# Sheet1.net
KiCad netlist of a schematic drawn in Altium Designer
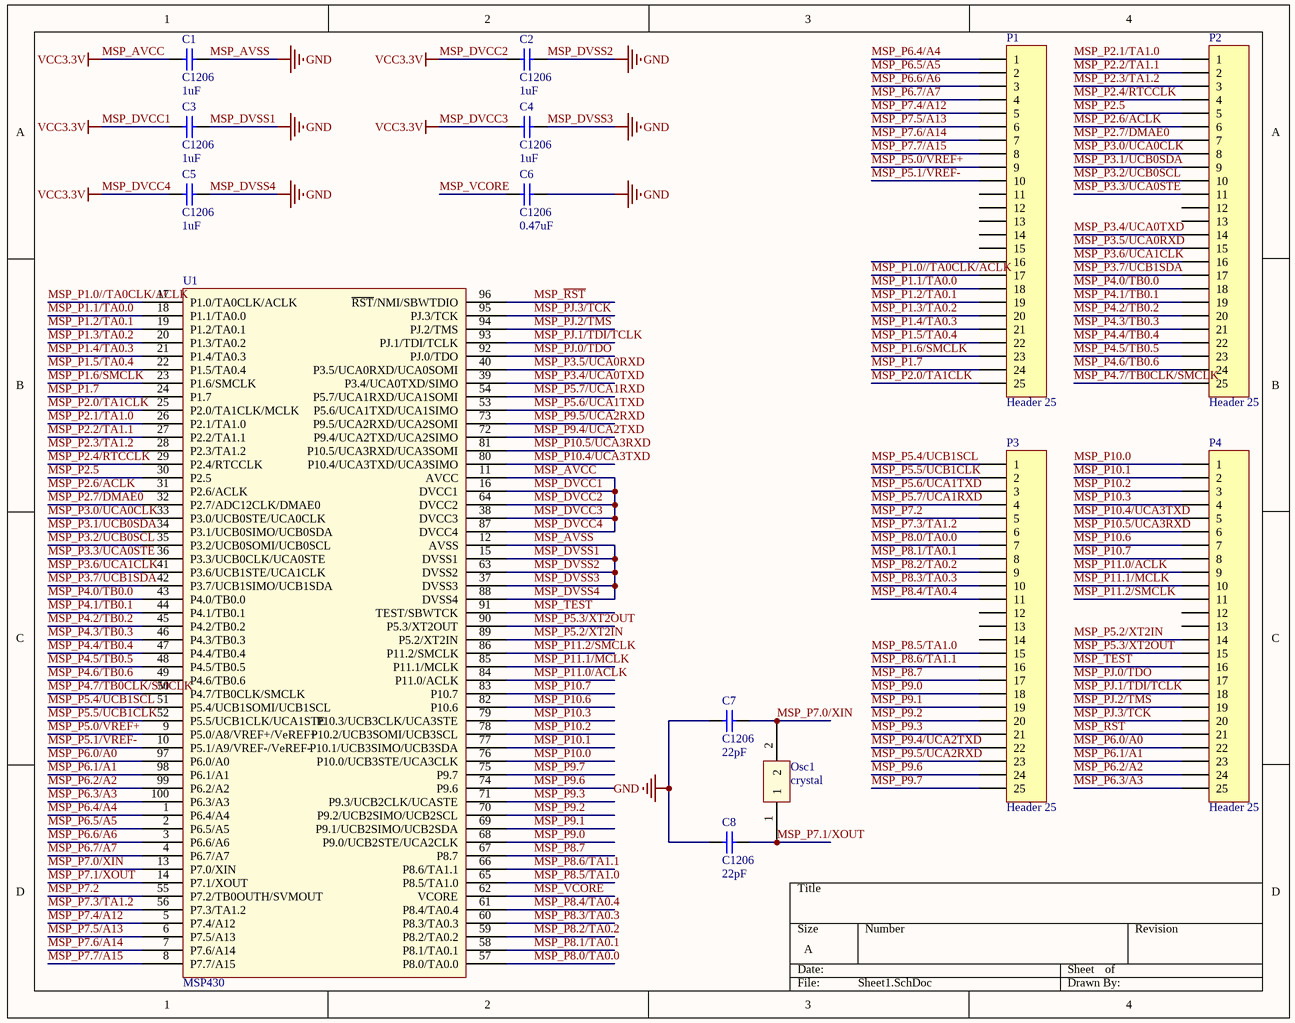
[diagram p0: Sheet1.SchDoc]

(export (version "E")
  (design (tool "Eeschema 10.0.6"))
  (components
    (comp (ref "C1")
      (value "C1206")
      (footprint "1206")
      (description "Ceramic Chip Capacitor - Standard")
      (fields (field (name "ALTIUM_VALUE") "1uF") (field (name "PUBLISHER") "Altium Limited"))
      (libsource (lib "KEMET Chip Capacitor") (part "C1206"))
    )
    (comp (ref "C2")
      (value "C1206")
      (footprint "1206")
      (description "Ceramic Chip Capacitor - Standard")
      (fields (field (name "ALTIUM_VALUE") "1uF") (field (name "PUBLISHER") "Altium Limited"))
      (libsource (lib "KEMET Chip Capacitor") (part "C1206"))
    )
    (comp (ref "C3")
      (value "C1206")
      (footprint "1206")
      (description "Ceramic Chip Capacitor - Standard")
      (fields (field (name "ALTIUM_VALUE") "1uF") (field (name "PUBLISHER") "Altium Limited"))
      (libsource (lib "KEMET Chip Capacitor") (part "C1206"))
    )
    (comp (ref "C4")
      (value "C1206")
      (footprint "1206")
      (description "Ceramic Chip Capacitor - Standard")
      (fields (field (name "ALTIUM_VALUE") "1uF") (field (name "PUBLISHER") "Altium Limited"))
      (libsource (lib "KEMET Chip Capacitor") (part "C1206"))
    )
    (comp (ref "C5")
      (value "C1206")
      (footprint "1206")
      (description "Ceramic Chip Capacitor - Standard")
      (fields (field (name "ALTIUM_VALUE") "1uF") (field (name "PUBLISHER") "Altium Limited"))
      (libsource (lib "KEMET Chip Capacitor") (part "C1206"))
    )
    (comp (ref "C6")
      (value "C1206")
      (footprint "1206")
      (description "Ceramic Chip Capacitor - Standard")
      (fields (field (name "ALTIUM_VALUE") "0.47uF") (field (name "PUBLISHER") "Altium Limited"))
      (libsource (lib "KEMET Chip Capacitor") (part "C1206"))
    )
    (comp (ref "C7")
      (value "C1206")
      (footprint "1206")
      (description "Ceramic Chip Capacitor - Standard")
      (fields (field (name "ALTIUM_VALUE") "22pF") (field (name "PUBLISHER") "Altium Limited"))
      (libsource (lib "KEMET Chip Capacitor") (part "C1206"))
    )
    (comp (ref "C8")
      (value "C1206")
      (footprint "1206")
      (description "Ceramic Chip Capacitor - Standard")
      (fields (field (name "ALTIUM_VALUE") "22pF") (field (name "PUBLISHER") "Altium Limited"))
      (libsource (lib "KEMET Chip Capacitor") (part "C1206"))
    )
    (comp (ref "Osc1")
      (value "crystal")
      (footprint "Crystal_32K:PCBComponent_1")
      (libsource (lib "Crystal_32K") (part "crystal"))
    )
    (comp (ref "P1")
      (value "Header 25")
      (footprint "HDR1X25")
      (description "Header, 25-Pin")
      (fields (field (name "PUBLISHER") "Altium Limited"))
      (libsource (lib "Miscellaneous Connectors") (part "Header 25"))
    )
    (comp (ref "P2")
      (value "Header 25")
      (footprint "HDR1X25")
      (description "Header, 25-Pin")
      (fields (field (name "PUBLISHER") "Altium Limited"))
      (libsource (lib "Miscellaneous Connectors") (part "Header 25"))
    )
    (comp (ref "P3")
      (value "Header 25")
      (footprint "HDR1X25")
      (description "Header, 25-Pin")
      (fields (field (name "PUBLISHER") "Altium Limited"))
      (libsource (lib "Miscellaneous Connectors") (part "Header 25"))
    )
    (comp (ref "P4")
      (value "Header 25")
      (footprint "HDR1X25")
      (description "Header, 25-Pin")
      (fields (field (name "PUBLISHER") "Altium Limited"))
      (libsource (lib "Miscellaneous Connectors") (part "Header 25"))
    )
    (comp (ref "U1")
      (value "MSP430")
      (footprint "MSP430F5438A:TSQFP50P1600X1600X160-100N")
      (libsource (lib "MSP430F5438A") (part "MSP430"))
    )
  )
  (nets
    (net (code "1") (name "/MSP_P1.0{slash}{slash}TA0CLK{slash}ACLK") (class "Default")
      (node (ref "P1") (pin "17") (pinfunction "17_17") (pintype "passive"))
      (node (ref "U1") (pin "17") (pinfunction "P1.0/TA0CLK/ACLK_17") (pintype "passive"))
    )
    (net (code "2") (name "/MSP_P1.1{slash}TA0.0") (class "Default")
      (node (ref "P1") (pin "18") (pinfunction "18_18") (pintype "passive"))
      (node (ref "U1") (pin "18") (pinfunction "P1.1/TA0.0_18") (pintype "passive"))
    )
    (net (code "3") (name "/MSP_P1.2{slash}TA0.1") (class "Default")
      (node (ref "P1") (pin "19") (pinfunction "19_19") (pintype "passive"))
      (node (ref "U1") (pin "19") (pinfunction "P1.2/TA0.1_19") (pintype "passive"))
    )
    (net (code "4") (name "/MSP_P1.3{slash}TA0.2") (class "Default")
      (node (ref "P1") (pin "20") (pinfunction "20_20") (pintype "passive"))
      (node (ref "U1") (pin "20") (pinfunction "P1.3/TA0.2_20") (pintype "passive"))
    )
    (net (code "5") (name "/MSP_P1.4{slash}TA0.3") (class "Default")
      (node (ref "P1") (pin "21") (pinfunction "21_21") (pintype "passive"))
      (node (ref "U1") (pin "21") (pinfunction "P1.4/TA0.3_21") (pintype "passive"))
    )
    (net (code "6") (name "/MSP_P1.5{slash}TA0.4") (class "Default")
      (node (ref "P1") (pin "22") (pinfunction "22_22") (pintype "passive"))
      (node (ref "U1") (pin "22") (pinfunction "P1.5/TA0.4_22") (pintype "passive"))
    )
    (net (code "7") (name "/MSP_P1.6{slash}SMCLK") (class "Default")
      (node (ref "P1") (pin "23") (pinfunction "23_23") (pintype "passive"))
      (node (ref "U1") (pin "23") (pinfunction "P1.6/SMCLK_23") (pintype "passive"))
    )
    (net (code "8") (name "/MSP_P1.7") (class "Default")
      (node (ref "P1") (pin "24") (pinfunction "24_24") (pintype "passive"))
      (node (ref "U1") (pin "24") (pinfunction "P1.7_24") (pintype "passive"))
    )
    (net (code "9") (name "/MSP_P2.0{slash}TA1CLK") (class "Default")
      (node (ref "P1") (pin "25") (pinfunction "25_25") (pintype "passive"))
      (node (ref "U1") (pin "25") (pinfunction "P2.0/TA1CLK/MCLK_25") (pintype "passive"))
    )
    (net (code "10") (name "/MSP_P2.1{slash}TA1.0") (class "Default")
      (node (ref "P2") (pin "1") (pinfunction "1_1") (pintype "passive"))
      (node (ref "U1") (pin "26") (pinfunction "P2.1/TA1.0_26") (pintype "passive"))
    )
    (net (code "11") (name "/MSP_P2.2{slash}TA1.1") (class "Default")
      (node (ref "P2") (pin "2") (pinfunction "2_2") (pintype "passive"))
      (node (ref "U1") (pin "27") (pinfunction "P2.2/TA1.1_27") (pintype "passive"))
    )
    (net (code "12") (name "/MSP_P2.3{slash}TA1.2") (class "Default")
      (node (ref "P2") (pin "3") (pinfunction "3_3") (pintype "passive"))
      (node (ref "U1") (pin "28") (pinfunction "P2.3/TA1.2_28") (pintype "passive"))
    )
    (net (code "13") (name "/MSP_P2.4{slash}RTCCLK") (class "Default")
      (node (ref "P2") (pin "4") (pinfunction "4_4") (pintype "passive"))
      (node (ref "U1") (pin "29") (pinfunction "P2.4/RTCCLK_29") (pintype "passive"))
    )
    (net (code "14") (name "/MSP_P2.5") (class "Default")
      (node (ref "P2") (pin "5") (pinfunction "5_5") (pintype "passive"))
      (node (ref "U1") (pin "30") (pinfunction "P2.5_30") (pintype "passive"))
    )
    (net (code "15") (name "/MSP_P2.6{slash}ACLK") (class "Default")
      (node (ref "P2") (pin "6") (pinfunction "6_6") (pintype "passive"))
      (node (ref "U1") (pin "31") (pinfunction "P2.6/ACLK_31") (pintype "passive"))
    )
    (net (code "16") (name "/MSP_P2.7{slash}DMAE0") (class "Default")
      (node (ref "P2") (pin "7") (pinfunction "7_7") (pintype "passive"))
      (node (ref "U1") (pin "32") (pinfunction "P2.7/ADC12CLK/DMAE0_32") (pintype "passive"))
    )
    (net (code "17") (name "/MSP_P3.0{slash}UCA0CLK") (class "Default")
      (node (ref "P2") (pin "8") (pinfunction "8_8") (pintype "passive"))
      (node (ref "U1") (pin "33") (pinfunction "P3.0/UCB0STE/UCA0CLK_33") (pintype "passive"))
    )
    (net (code "18") (name "/MSP_P3.1{slash}UCB0SDA") (class "Default")
      (node (ref "P2") (pin "9") (pinfunction "9_9") (pintype "passive"))
      (node (ref "U1") (pin "34") (pinfunction "P3.1/UCB0SIMO/UCB0SDA_34") (pintype "passive"))
    )
    (net (code "19") (name "/MSP_P3.2{slash}UCB0SCL") (class "Default")
      (node (ref "P2") (pin "10") (pinfunction "10_10") (pintype "passive"))
      (node (ref "U1") (pin "35") (pinfunction "P3.2/UCB0SOMI/UCB0SCL_35") (pintype "passive"))
    )
    (net (code "20") (name "/MSP_P3.3{slash}UCA0STE") (class "Default")
      (node (ref "P2") (pin "11") (pinfunction "11_11") (pintype "passive"))
      (node (ref "U1") (pin "36") (pinfunction "P3.3/UCB0CLK/UCA0STE_36") (pintype "passive"))
    )
    (net (code "21") (name "/MSP_P3.4{slash}UCA0TXD") (class "Default")
      (node (ref "P2") (pin "14") (pinfunction "14_14") (pintype "passive"))
      (node (ref "U1") (pin "39") (pinfunction "P3.4/UCA0TXD/SIMO_39") (pintype "passive"))
    )
    (net (code "22") (name "/MSP_P3.5{slash}UCA0RXD") (class "Default")
      (node (ref "P2") (pin "15") (pinfunction "15_15") (pintype "passive"))
      (node (ref "U1") (pin "40") (pinfunction "P3.5/UCA0RXD/UCA0SOMI_40") (pintype "passive"))
    )
    (net (code "23") (name "/MSP_P3.6{slash}UCA1CLK") (class "Default")
      (node (ref "P2") (pin "16") (pinfunction "16_16") (pintype "passive"))
      (node (ref "U1") (pin "41") (pinfunction "P3.6/UCB1STE/UCA1CLK_41") (pintype "passive"))
    )
    (net (code "24") (name "/MSP_P3.7{slash}UCB1SDA") (class "Default")
      (node (ref "P2") (pin "17") (pinfunction "17_17") (pintype "passive"))
      (node (ref "U1") (pin "42") (pinfunction "P3.7/UCB1SIMO/UCB1SDA_42") (pintype "passive"))
    )
    (net (code "25") (name "/MSP_P4.0{slash}TB0.0") (class "Default")
      (node (ref "P2") (pin "18") (pinfunction "18_18") (pintype "passive"))
      (node (ref "U1") (pin "43") (pinfunction "P4.0/TB0.0_43") (pintype "passive"))
    )
    (net (code "26") (name "/MSP_P4.1{slash}TB0.1") (class "Default")
      (node (ref "P2") (pin "19") (pinfunction "19_19") (pintype "passive"))
      (node (ref "U1") (pin "44") (pinfunction "P4.1/TB0.1_44") (pintype "passive"))
    )
    (net (code "27") (name "/MSP_P4.2{slash}TB0.2") (class "Default")
      (node (ref "P2") (pin "20") (pinfunction "20_20") (pintype "passive"))
      (node (ref "U1") (pin "45") (pinfunction "P4.2/TB0.2_45") (pintype "passive"))
    )
    (net (code "28") (name "/MSP_P4.3{slash}TB0.3") (class "Default")
      (node (ref "P2") (pin "21") (pinfunction "21_21") (pintype "passive"))
      (node (ref "U1") (pin "46") (pinfunction "P4.3/TB0.3_46") (pintype "passive"))
    )
    (net (code "29") (name "/MSP_P4.4{slash}TB0.4") (class "Default")
      (node (ref "P2") (pin "22") (pinfunction "22_22") (pintype "passive"))
      (node (ref "U1") (pin "47") (pinfunction "P4.4/TB0.4_47") (pintype "passive"))
    )
    (net (code "30") (name "/MSP_P4.5{slash}TB0.5") (class "Default")
      (node (ref "P2") (pin "23") (pinfunction "23_23") (pintype "passive"))
      (node (ref "U1") (pin "48") (pinfunction "P4.5/TB0.5_48") (pintype "passive"))
    )
    (net (code "31") (name "/MSP_P4.6{slash}TB0.6") (class "Default")
      (node (ref "P2") (pin "24") (pinfunction "24_24") (pintype "passive"))
      (node (ref "U1") (pin "49") (pinfunction "P4.6/TB0.6_49") (pintype "passive"))
    )
    (net (code "32") (name "/MSP_P4.7{slash}TB0CLK{slash}SMCLK") (class "Default")
      (node (ref "P2") (pin "25") (pinfunction "25_25") (pintype "passive"))
      (node (ref "U1") (pin "50") (pinfunction "P4.7/TB0CLK/SMCLK_50") (pintype "passive"))
    )
    (net (code "33") (name "/MSP_P5.0{slash}VREF+") (class "Default")
      (node (ref "P1") (pin "9") (pinfunction "9_9") (pintype "passive"))
      (node (ref "U1") (pin "9") (pinfunction "P5.0/A8/VREF+/VeREF+_9") (pintype "passive"))
    )
    (net (code "34") (name "/MSP_P5.1{slash}VREF-") (class "Default")
      (node (ref "P1") (pin "10") (pinfunction "10_10") (pintype "passive"))
      (node (ref "U1") (pin "10") (pinfunction "P5.1/A9/VREF-/VeREF-_10") (pintype "passive"))
    )
    (net (code "35") (name "/MSP_P5.2{slash}XT2IN") (class "Default")
      (node (ref "P4") (pin "14") (pinfunction "14_14") (pintype "passive"))
      (node (ref "U1") (pin "89") (pinfunction "P5.2/XT2IN_89") (pintype "passive"))
    )
    (net (code "36") (name "/MSP_P5.3{slash}XT2OUT") (class "Default")
      (node (ref "P4") (pin "15") (pinfunction "15_15") (pintype "passive"))
      (node (ref "U1") (pin "90") (pinfunction "P5.3/XT2OUT_90") (pintype "passive"))
    )
    (net (code "37") (name "/MSP_P5.4{slash}UCB1SCL") (class "Default")
      (node (ref "P3") (pin "1") (pinfunction "1_1") (pintype "passive"))
      (node (ref "U1") (pin "51") (pinfunction "P5.4/UCB1SOMI/UCB1SCL_51") (pintype "passive"))
    )
    (net (code "38") (name "/MSP_P5.5{slash}UCB1CLK") (class "Default")
      (node (ref "P3") (pin "2") (pinfunction "2_2") (pintype "passive"))
      (node (ref "U1") (pin "52") (pinfunction "P5.5/UCB1CLK/UCA1STE_52") (pintype "passive"))
    )
    (net (code "39") (name "/MSP_P5.6{slash}UCA1TXD") (class "Default")
      (node (ref "P3") (pin "3") (pinfunction "3_3") (pintype "passive"))
      (node (ref "U1") (pin "53") (pinfunction "P5.6/UCA1TXD/UCA1SIMO_53") (pintype "passive"))
    )
    (net (code "40") (name "/MSP_P5.7{slash}UCA1RXD") (class "Default")
      (node (ref "P3") (pin "4") (pinfunction "4_4") (pintype "passive"))
      (node (ref "U1") (pin "54") (pinfunction "P5.7/UCA1RXD/UCA1SOMI_54") (pintype "passive"))
    )
    (net (code "41") (name "/MSP_P6.0{slash}A0") (class "Default")
      (node (ref "P4") (pin "22") (pinfunction "22_22") (pintype "passive"))
      (node (ref "U1") (pin "97") (pinfunction "P6.0/A0_97") (pintype "passive"))
    )
    (net (code "42") (name "/MSP_P6.1{slash}A1") (class "Default")
      (node (ref "P4") (pin "23") (pinfunction "23_23") (pintype "passive"))
      (node (ref "U1") (pin "98") (pinfunction "P6.1/A1_98") (pintype "passive"))
    )
    (net (code "43") (name "/MSP_P6.2{slash}A2") (class "Default")
      (node (ref "P4") (pin "24") (pinfunction "24_24") (pintype "passive"))
      (node (ref "U1") (pin "99") (pinfunction "P6.2/A2_99") (pintype "passive"))
    )
    (net (code "44") (name "/MSP_P6.3{slash}A3") (class "Default")
      (node (ref "P4") (pin "25") (pinfunction "25_25") (pintype "passive"))
      (node (ref "U1") (pin "100") (pinfunction "P6.3/A3_100") (pintype "passive"))
    )
    (net (code "45") (name "/MSP_P6.4{slash}A4") (class "Default")
      (node (ref "P1") (pin "1") (pinfunction "1_1") (pintype "passive"))
      (node (ref "U1") (pin "1") (pinfunction "P6.4/A4_1") (pintype "passive"))
    )
    (net (code "46") (name "/MSP_P6.5{slash}A5") (class "Default")
      (node (ref "P1") (pin "2") (pinfunction "2_2") (pintype "passive"))
      (node (ref "U1") (pin "2") (pinfunction "P6.5/A5_2") (pintype "passive"))
    )
    (net (code "47") (name "/MSP_P6.6{slash}A6") (class "Default")
      (node (ref "P1") (pin "3") (pinfunction "3_3") (pintype "passive"))
      (node (ref "U1") (pin "3") (pinfunction "P6.6/A6_3") (pintype "passive"))
    )
    (net (code "48") (name "/MSP_P6.7{slash}A7") (class "Default")
      (node (ref "P1") (pin "4") (pinfunction "4_4") (pintype "passive"))
      (node (ref "U1") (pin "4") (pinfunction "P6.7/A7_4") (pintype "passive"))
    )
    (net (code "49") (name "/MSP_P7.0{slash}XIN") (class "Default")
      (node (ref "C7") (pin "2") (pinfunction "2_2") (pintype "passive"))
      (node (ref "Osc1") (pin "2") (pinfunction "2_2") (pintype "passive"))
      (node (ref "U1") (pin "13") (pinfunction "P7.0/XIN_13") (pintype "passive"))
    )
    (net (code "50") (name "/MSP_P7.1{slash}XOUT") (class "Default")
      (node (ref "C8") (pin "2") (pinfunction "2_2") (pintype "passive"))
      (node (ref "Osc1") (pin "1") (pinfunction "1_1") (pintype "passive"))
      (node (ref "U1") (pin "14") (pinfunction "P7.1/XOUT_14") (pintype "passive"))
    )
    (net (code "51") (name "/MSP_P7.2") (class "Default")
      (node (ref "P3") (pin "5") (pinfunction "5_5") (pintype "passive"))
      (node (ref "U1") (pin "55") (pinfunction "P7.2/TB0OUTH/SVMOUT_55") (pintype "passive"))
    )
    (net (code "52") (name "/MSP_P7.3{slash}TA1.2") (class "Default")
      (node (ref "P3") (pin "6") (pinfunction "6_6") (pintype "passive"))
      (node (ref "U1") (pin "56") (pinfunction "P7.3/TA1.2_56") (pintype "passive"))
    )
    (net (code "53") (name "/MSP_P7.4{slash}A12") (class "Default")
      (node (ref "P1") (pin "5") (pinfunction "5_5") (pintype "passive"))
      (node (ref "U1") (pin "5") (pinfunction "P7.4/A12_5") (pintype "passive"))
    )
    (net (code "54") (name "/MSP_P7.5{slash}A13") (class "Default")
      (node (ref "P1") (pin "6") (pinfunction "6_6") (pintype "passive"))
      (node (ref "U1") (pin "6") (pinfunction "P7.5/A13_6") (pintype "passive"))
    )
    (net (code "55") (name "/MSP_P7.6{slash}A14") (class "Default")
      (node (ref "P1") (pin "7") (pinfunction "7_7") (pintype "passive"))
      (node (ref "U1") (pin "7") (pinfunction "P7.6/A14_7") (pintype "passive"))
    )
    (net (code "56") (name "/MSP_P7.7{slash}A15") (class "Default")
      (node (ref "P1") (pin "8") (pinfunction "8_8") (pintype "passive"))
      (node (ref "U1") (pin "8") (pinfunction "P7.7/A15_8") (pintype "passive"))
    )
    (net (code "57") (name "/MSP_P8.0{slash}TA0.0") (class "Default")
      (node (ref "P3") (pin "7") (pinfunction "7_7") (pintype "passive"))
      (node (ref "U1") (pin "57") (pinfunction "P8.0/TA0.0_57") (pintype "passive"))
    )
    (net (code "58") (name "/MSP_P8.1{slash}TA0.1") (class "Default")
      (node (ref "P3") (pin "8") (pinfunction "8_8") (pintype "passive"))
      (node (ref "U1") (pin "58") (pinfunction "P8.1/TA0.1_58") (pintype "passive"))
    )
    (net (code "59") (name "/MSP_P8.2{slash}TA0.2") (class "Default")
      (node (ref "P3") (pin "9") (pinfunction "9_9") (pintype "passive"))
      (node (ref "U1") (pin "59") (pinfunction "P8.2/TA0.2_59") (pintype "passive"))
    )
    (net (code "60") (name "/MSP_P8.3{slash}TA0.3") (class "Default")
      (node (ref "P3") (pin "10") (pinfunction "10_10") (pintype "passive"))
      (node (ref "U1") (pin "60") (pinfunction "P8.3/TA0.3_60") (pintype "passive"))
    )
    (net (code "61") (name "/MSP_P8.4{slash}TA0.4") (class "Default")
      (node (ref "P3") (pin "11") (pinfunction "11_11") (pintype "passive"))
      (node (ref "U1") (pin "61") (pinfunction "P8.4/TA0.4_61") (pintype "passive"))
    )
    (net (code "62") (name "/MSP_P8.5{slash}TA1.0") (class "Default")
      (node (ref "P3") (pin "15") (pinfunction "15_15") (pintype "passive"))
      (node (ref "U1") (pin "65") (pinfunction "P8.5/TA1.0_65") (pintype "passive"))
    )
    (net (code "63") (name "/MSP_P8.6{slash}TA1.1") (class "Default")
      (node (ref "P3") (pin "16") (pinfunction "16_16") (pintype "passive"))
      (node (ref "U1") (pin "66") (pinfunction "P8.6/TA1.1_66") (pintype "passive"))
    )
    (net (code "64") (name "/MSP_P8.7") (class "Default")
      (node (ref "P3") (pin "17") (pinfunction "17_17") (pintype "passive"))
      (node (ref "U1") (pin "67") (pinfunction "P8.7_67") (pintype "passive"))
    )
    (net (code "65") (name "/MSP_P9.0") (class "Default")
      (node (ref "P3") (pin "18") (pinfunction "18_18") (pintype "passive"))
      (node (ref "U1") (pin "68") (pinfunction "P9.0/UCB2STE/UCA2CLK_68") (pintype "passive"))
    )
    (net (code "66") (name "/MSP_P9.1") (class "Default")
      (node (ref "P3") (pin "19") (pinfunction "19_19") (pintype "passive"))
      (node (ref "U1") (pin "69") (pinfunction "P9.1/UCB2SIMO/UCB2SDA_69") (pintype "passive"))
    )
    (net (code "67") (name "/MSP_P9.2") (class "Default")
      (node (ref "P3") (pin "20") (pinfunction "20_20") (pintype "passive"))
      (node (ref "U1") (pin "70") (pinfunction "P9.2/UCB2SIMO/UCB2SCL_70") (pintype "passive"))
    )
    (net (code "68") (name "/MSP_P9.3") (class "Default")
      (node (ref "P3") (pin "21") (pinfunction "21_21") (pintype "passive"))
      (node (ref "U1") (pin "71") (pinfunction "P9.3/UCB2CLK/UCASTE_71") (pintype "passive"))
    )
    (net (code "69") (name "/MSP_P9.4{slash}UCA2TXD") (class "Default")
      (node (ref "P3") (pin "22") (pinfunction "22_22") (pintype "passive"))
      (node (ref "U1") (pin "72") (pinfunction "P9.4/UCA2TXD/UCA2SIMO_72") (pintype "passive"))
    )
    (net (code "70") (name "/MSP_P9.5{slash}UCA2RXD") (class "Default")
      (node (ref "P3") (pin "23") (pinfunction "23_23") (pintype "passive"))
      (node (ref "U1") (pin "73") (pinfunction "P9.5/UCA2RXD/UCA2SOMI_73") (pintype "passive"))
    )
    (net (code "71") (name "/MSP_P9.6") (class "Default")
      (node (ref "P3") (pin "24") (pinfunction "24_24") (pintype "passive"))
      (node (ref "U1") (pin "74") (pinfunction "P9.6_74") (pintype "passive"))
    )
    (net (code "72") (name "/MSP_P9.7") (class "Default")
      (node (ref "P3") (pin "25") (pinfunction "25_25") (pintype "passive"))
      (node (ref "U1") (pin "75") (pinfunction "P9.7_75") (pintype "passive"))
    )
    (net (code "73") (name "/MSP_P10.0") (class "Default")
      (node (ref "P4") (pin "1") (pinfunction "1_1") (pintype "passive"))
      (node (ref "U1") (pin "76") (pinfunction "P10.0/UCB3STE/UCA3CLK_76") (pintype "passive"))
    )
    (net (code "74") (name "/MSP_P10.1") (class "Default")
      (node (ref "P4") (pin "2") (pinfunction "2_2") (pintype "passive"))
      (node (ref "U1") (pin "77") (pinfunction "P10.1/UCB3SIMO/UCB3SDA_77") (pintype "passive"))
    )
    (net (code "75") (name "/MSP_P10.2") (class "Default")
      (node (ref "P4") (pin "3") (pinfunction "3_3") (pintype "passive"))
      (node (ref "U1") (pin "78") (pinfunction "P10.2/UCB3SOMI/UCB3SCL_78") (pintype "passive"))
    )
    (net (code "76") (name "/MSP_P10.3") (class "Default")
      (node (ref "P4") (pin "4") (pinfunction "4_4") (pintype "passive"))
      (node (ref "U1") (pin "79") (pinfunction "P10.3/UCB3CLK/UCA3STE_79") (pintype "passive"))
    )
    (net (code "77") (name "/MSP_P10.4{slash}UCA3TXD") (class "Default")
      (node (ref "P4") (pin "5") (pinfunction "5_5") (pintype "passive"))
      (node (ref "U1") (pin "80") (pinfunction "P10.4/UCA3TXD/UCA3SIMO_80") (pintype "passive"))
    )
    (net (code "78") (name "/MSP_P10.5{slash}UCA3RXD") (class "Default")
      (node (ref "P4") (pin "6") (pinfunction "6_6") (pintype "passive"))
      (node (ref "U1") (pin "81") (pinfunction "P10.5/UCA3RXD/UCA3SOMI_81") (pintype "passive"))
    )
    (net (code "79") (name "/MSP_P10.6") (class "Default")
      (node (ref "P4") (pin "7") (pinfunction "7_7") (pintype "passive"))
      (node (ref "U1") (pin "82") (pinfunction "P10.6_82") (pintype "passive"))
    )
    (net (code "80") (name "/MSP_P10.7") (class "Default")
      (node (ref "P4") (pin "8") (pinfunction "8_8") (pintype "passive"))
      (node (ref "U1") (pin "83") (pinfunction "P10.7_83") (pintype "passive"))
    )
    (net (code "81") (name "/MSP_P11.0{slash}ACLK") (class "Default")
      (node (ref "P4") (pin "9") (pinfunction "9_9") (pintype "passive"))
      (node (ref "U1") (pin "84") (pinfunction "P11.0/ACLK_84") (pintype "passive"))
    )
    (net (code "82") (name "/MSP_P11.1{slash}MCLK") (class "Default")
      (node (ref "P4") (pin "10") (pinfunction "10_10") (pintype "passive"))
      (node (ref "U1") (pin "85") (pinfunction "P11.1/MCLK_85") (pintype "passive"))
    )
    (net (code "83") (name "/MSP_P11.2{slash}SMCLK") (class "Default")
      (node (ref "P4") (pin "11") (pinfunction "11_11") (pintype "passive"))
      (node (ref "U1") (pin "86") (pinfunction "P11.2/SMCLK_86") (pintype "passive"))
    )
    (net (code "84") (name "/MSP_PJ.0{slash}TDO") (class "Default")
      (node (ref "P4") (pin "17") (pinfunction "17_17") (pintype "passive"))
      (node (ref "U1") (pin "92") (pinfunction "PJ.0/TDO_92") (pintype "passive"))
    )
    (net (code "85") (name "/MSP_PJ.1{slash}TDI{slash}TCLK") (class "Default")
      (node (ref "P4") (pin "18") (pinfunction "18_18") (pintype "passive"))
      (node (ref "U1") (pin "93") (pinfunction "PJ.1/TDI/TCLK_93") (pintype "passive"))
    )
    (net (code "86") (name "/MSP_PJ.2{slash}TMS") (class "Default")
      (node (ref "P4") (pin "19") (pinfunction "19_19") (pintype "passive"))
      (node (ref "U1") (pin "94") (pinfunction "PJ.2/TMS_94") (pintype "passive"))
    )
    (net (code "87") (name "/MSP_PJ.3{slash}TCK") (class "Default")
      (node (ref "P4") (pin "20") (pinfunction "20_20") (pintype "passive"))
      (node (ref "U1") (pin "95") (pinfunction "PJ.3/TCK_95") (pintype "passive"))
    )
    (net (code "88") (name "/MSP_TEST") (class "Default")
      (node (ref "P4") (pin "16") (pinfunction "16_16") (pintype "passive"))
      (node (ref "U1") (pin "91") (pinfunction "TEST/SBWTCK_91") (pintype "passive"))
    )
    (net (code "89") (name "/MSP_VCORE") (class "Default")
      (node (ref "C6") (pin "1") (pinfunction "1_1") (pintype "passive"))
      (node (ref "U1") (pin "62") (pinfunction "VCORE_62") (pintype "passive"))
    )
    (net (code "90") (name "/MSP_~{RST}") (class "Default")
      (node (ref "P4") (pin "21") (pinfunction "21_21") (pintype "passive"))
      (node (ref "U1") (pin "96") (pinfunction "~{RST}/NMI/SBWTDIO_96") (pintype "passive"))
    )
    (net (code "91") (name "GND") (class "Default")
      (node (ref "C1") (pin "2") (pinfunction "2_2") (pintype "passive"))
      (node (ref "C2") (pin "2") (pinfunction "2_2") (pintype "passive"))
      (node (ref "C3") (pin "2") (pinfunction "2_2") (pintype "passive"))
      (node (ref "C4") (pin "2") (pinfunction "2_2") (pintype "passive"))
      (node (ref "C5") (pin "2") (pinfunction "2_2") (pintype "passive"))
      (node (ref "C6") (pin "2") (pinfunction "2_2") (pintype "passive"))
      (node (ref "C7") (pin "1") (pinfunction "1_1") (pintype "passive"))
      (node (ref "C8") (pin "1") (pinfunction "1_1") (pintype "passive"))
      (node (ref "U1") (pin "12") (pinfunction "AVSS_12") (pintype "passive"))
      (node (ref "U1") (pin "15") (pinfunction "DVSS1_15") (pintype "power_in"))
      (node (ref "U1") (pin "37") (pinfunction "DVSS3_37") (pintype "power_in"))
      (node (ref "U1") (pin "63") (pinfunction "DVSS2_63") (pintype "power_in"))
      (node (ref "U1") (pin "88") (pinfunction "DVSS4_88") (pintype "power_in"))
    )
    (net (code "92") (name "VCC3.3V") (class "Default")
      (node (ref "C1") (pin "1") (pinfunction "1_1") (pintype "passive"))
      (node (ref "C2") (pin "1") (pinfunction "1_1") (pintype "passive"))
      (node (ref "C3") (pin "1") (pinfunction "1_1") (pintype "passive"))
      (node (ref "C4") (pin "1") (pinfunction "1_1") (pintype "passive"))
      (node (ref "C5") (pin "1") (pinfunction "1_1") (pintype "passive"))
      (node (ref "U1") (pin "11") (pinfunction "AVCC_11") (pintype "passive"))
      (node (ref "U1") (pin "16") (pinfunction "DVCC1_16") (pintype "power_in"))
      (node (ref "U1") (pin "38") (pinfunction "DVCC3_38") (pintype "power_in"))
      (node (ref "U1") (pin "64") (pinfunction "DVCC2_64") (pintype "power_in"))
      (node (ref "U1") (pin "87") (pinfunction "DVCC4_87") (pintype "power_in"))
    )
    (net (code "93") (name "unconnected-(P1-Pad11)") (class "Default")
      (node (ref "P1") (pin "11") (pinfunction "11_11") (pintype "passive"))
    )
    (net (code "94") (name "unconnected-(P1-Pad12)") (class "Default")
      (node (ref "P1") (pin "12") (pinfunction "12_12") (pintype "passive"))
    )
    (net (code "95") (name "unconnected-(P1-Pad13)") (class "Default")
      (node (ref "P1") (pin "13") (pinfunction "13_13") (pintype "passive"))
    )
    (net (code "96") (name "unconnected-(P1-Pad14)") (class "Default")
      (node (ref "P1") (pin "14") (pinfunction "14_14") (pintype "passive"))
    )
    (net (code "97") (name "unconnected-(P1-Pad15)") (class "Default")
      (node (ref "P1") (pin "15") (pinfunction "15_15") (pintype "passive"))
    )
    (net (code "98") (name "unconnected-(P1-Pad16)") (class "Default")
      (node (ref "P1") (pin "16") (pinfunction "16_16") (pintype "passive"))
    )
    (net (code "99") (name "unconnected-(P2-Pad12)") (class "Default")
      (node (ref "P2") (pin "12") (pinfunction "12_12") (pintype "passive"))
    )
    (net (code "100") (name "unconnected-(P2-Pad13)") (class "Default")
      (node (ref "P2") (pin "13") (pinfunction "13_13") (pintype "passive"))
    )
    (net (code "101") (name "unconnected-(P3-Pad12)") (class "Default")
      (node (ref "P3") (pin "12") (pinfunction "12_12") (pintype "passive"))
    )
    (net (code "102") (name "unconnected-(P3-Pad13)") (class "Default")
      (node (ref "P3") (pin "13") (pinfunction "13_13") (pintype "passive"))
    )
    (net (code "103") (name "unconnected-(P3-Pad14)") (class "Default")
      (node (ref "P3") (pin "14") (pinfunction "14_14") (pintype "passive"))
    )
    (net (code "104") (name "unconnected-(P4-Pad12)") (class "Default")
      (node (ref "P4") (pin "12") (pinfunction "12_12") (pintype "passive"))
    )
    (net (code "105") (name "unconnected-(P4-Pad13)") (class "Default")
      (node (ref "P4") (pin "13") (pinfunction "13_13") (pintype "passive"))
    )
  )
)
